# Digital_Port_A_State_LED_Inducator.net
KiCad netlist of a schematic drawn in Altium Designer
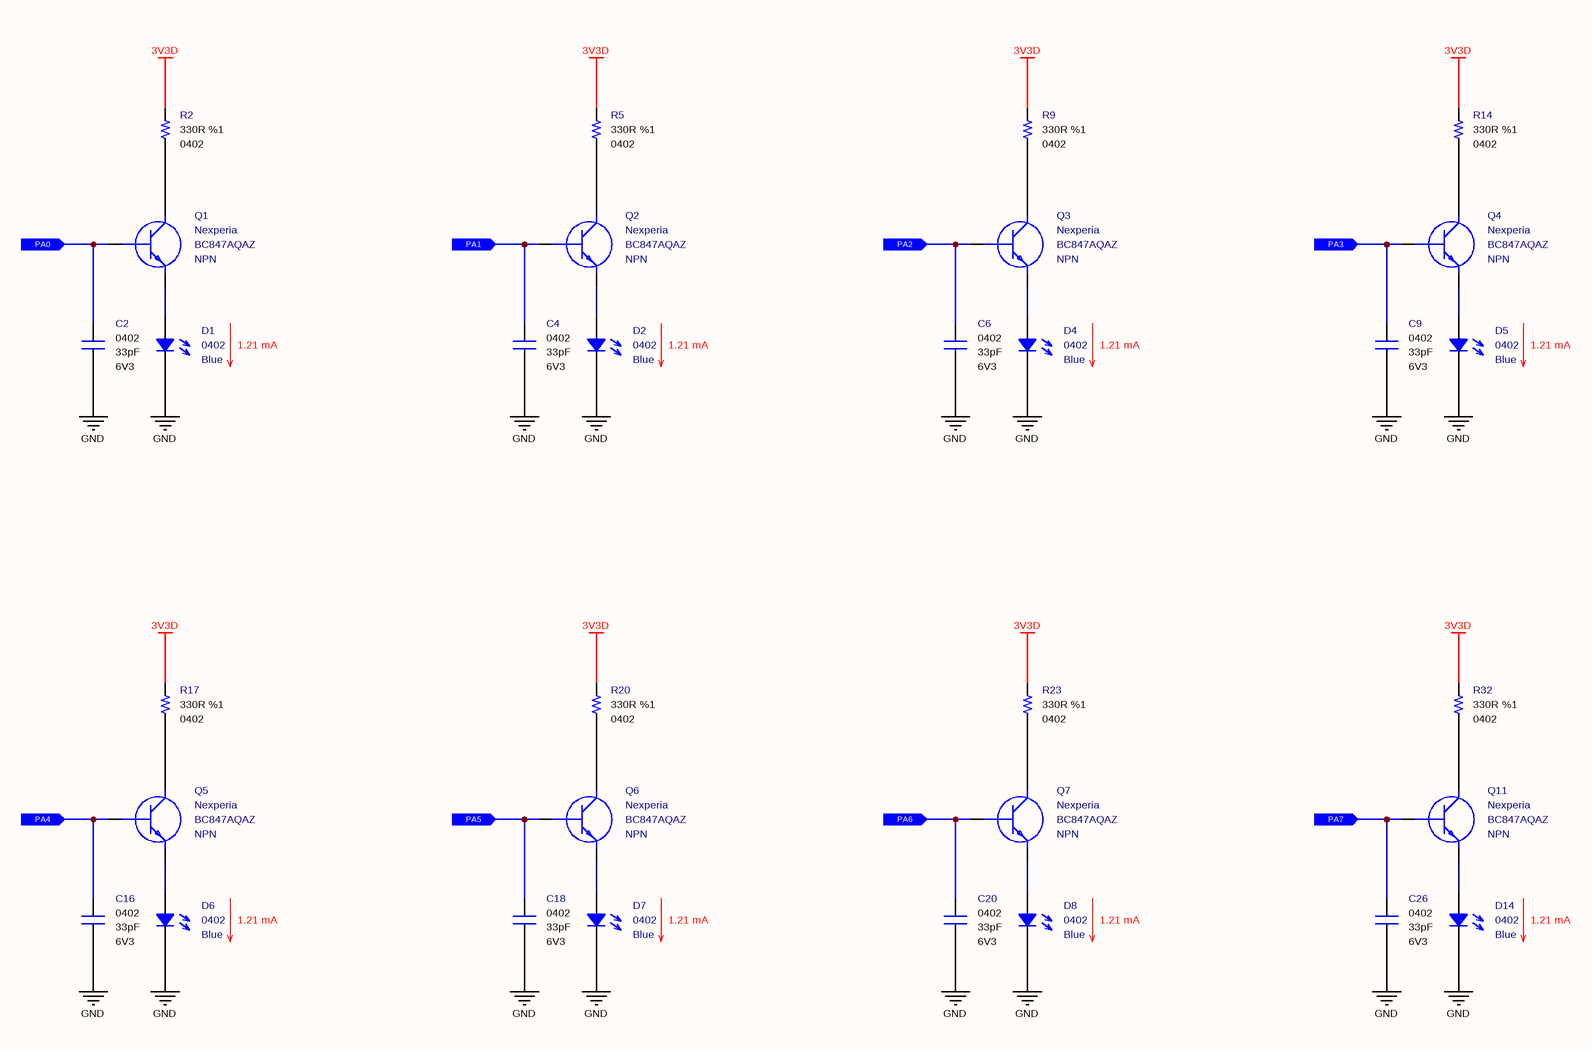
[diagram p0: Digital Port A State LED Inducator.SchDoc]

(export (version "E")
  (design (tool "Eeschema 10.0.6"))
  (components
    (comp (ref "C2")
      (value "33pF")
      (footprint "CAPACITOR_0402")
      (description "Capacitor - 33pF [0402] (Ceramic)")
      (fields
        (field (name "CASE") "0402")
        (field (name "TOLERANCE") "10%")
        (field (name "VOLTAGE") "6V3")
        (field (name "MANUFACTURER PART NUMBER") "C0402C330J9RACAUTO")
      )
      (libsource (lib "Ovoo_Library") (part "Capacitor - 33pF [0402-6V3]"))
    )
    (comp (ref "C4")
      (value "33pF")
      (footprint "CAPACITOR_0402")
      (description "Capacitor - 33pF [0402] (Ceramic)")
      (fields
        (field (name "CASE") "0402")
        (field (name "TOLERANCE") "10%")
        (field (name "VOLTAGE") "6V3")
        (field (name "MANUFACTURER PART NUMBER") "C0402C330J9RACAUTO")
      )
      (libsource (lib "Ovoo_Library") (part "Capacitor - 33pF [0402-6V3]"))
    )
    (comp (ref "C6")
      (value "33pF")
      (footprint "CAPACITOR_0402")
      (description "Capacitor - 33pF [0402] (Ceramic)")
      (fields
        (field (name "CASE") "0402")
        (field (name "TOLERANCE") "10%")
        (field (name "VOLTAGE") "6V3")
        (field (name "MANUFACTURER PART NUMBER") "C0402C330J9RACAUTO")
      )
      (libsource (lib "Ovoo_Library") (part "Capacitor - 33pF [0402-6V3]"))
    )
    (comp (ref "C9")
      (value "33pF")
      (footprint "CAPACITOR_0402")
      (description "Capacitor - 33pF [0402] (Ceramic)")
      (fields
        (field (name "CASE") "0402")
        (field (name "TOLERANCE") "10%")
        (field (name "VOLTAGE") "6V3")
        (field (name "MANUFACTURER PART NUMBER") "C0402C330J9RACAUTO")
      )
      (libsource (lib "Ovoo_Library") (part "Capacitor - 33pF [0402-6V3]"))
    )
    (comp (ref "C16")
      (value "33pF")
      (footprint "CAPACITOR_0402")
      (description "Capacitor - 33pF [0402] (Ceramic)")
      (fields
        (field (name "CASE") "0402")
        (field (name "TOLERANCE") "10%")
        (field (name "VOLTAGE") "6V3")
        (field (name "MANUFACTURER PART NUMBER") "C0402C330J9RACAUTO")
      )
      (libsource (lib "Ovoo_Library") (part "Capacitor - 33pF [0402-6V3]"))
    )
    (comp (ref "C18")
      (value "33pF")
      (footprint "CAPACITOR_0402")
      (description "Capacitor - 33pF [0402] (Ceramic)")
      (fields
        (field (name "CASE") "0402")
        (field (name "TOLERANCE") "10%")
        (field (name "VOLTAGE") "6V3")
        (field (name "MANUFACTURER PART NUMBER") "C0402C330J9RACAUTO")
      )
      (libsource (lib "Ovoo_Library") (part "Capacitor - 33pF [0402-6V3]"))
    )
    (comp (ref "C20")
      (value "33pF")
      (footprint "CAPACITOR_0402")
      (description "Capacitor - 33pF [0402] (Ceramic)")
      (fields
        (field (name "CASE") "0402")
        (field (name "TOLERANCE") "10%")
        (field (name "VOLTAGE") "6V3")
        (field (name "MANUFACTURER PART NUMBER") "C0402C330J9RACAUTO")
      )
      (libsource (lib "Ovoo_Library") (part "Capacitor - 33pF [0402-6V3]"))
    )
    (comp (ref "C26")
      (value "33pF")
      (footprint "CAPACITOR_0402")
      (description "Capacitor - 33pF [0402] (Ceramic)")
      (fields
        (field (name "CASE") "0402")
        (field (name "TOLERANCE") "10%")
        (field (name "VOLTAGE") "6V3")
        (field (name "MANUFACTURER PART NUMBER") "C0402C330J9RACAUTO")
      )
      (libsource (lib "Ovoo_Library") (part "Capacitor - 33pF [0402-6V3]"))
    )
    (comp (ref "D1")
      (value "SMD LED (Blue)")
      (footprint "LED_0402")
      (description "Standard LEDs - SMD PICOLEDTM;BLUE LED; 25M @ 5MA")
      (fields
        (field (name "MANUFACTURER_PART_NUMBER") "SMLP13BC8TT86")
        (field (name "MOUSER_PART_NUMBER") "755-SMLP13BC8TT86")
        (field (name "CASE") "0402")
        (field (name "COLOR") "Blue")
      )
      (libsource (lib "Ovoo_Library") (part "Diode - LED (0402-Blue)"))
    )
    (comp (ref "D2")
      (value "SMD LED (Blue)")
      (footprint "LED_0402")
      (description "Standard LEDs - SMD PICOLEDTM;BLUE LED; 25M @ 5MA")
      (fields
        (field (name "MANUFACTURER_PART_NUMBER") "SMLP13BC8TT86")
        (field (name "MOUSER_PART_NUMBER") "755-SMLP13BC8TT86")
        (field (name "CASE") "0402")
        (field (name "COLOR") "Blue")
      )
      (libsource (lib "Ovoo_Library") (part "Diode - LED (0402-Blue)"))
    )
    (comp (ref "D4")
      (value "SMD LED (Blue)")
      (footprint "LED_0402")
      (description "Standard LEDs - SMD PICOLEDTM;BLUE LED; 25M @ 5MA")
      (fields
        (field (name "MANUFACTURER_PART_NUMBER") "SMLP13BC8TT86")
        (field (name "MOUSER_PART_NUMBER") "755-SMLP13BC8TT86")
        (field (name "CASE") "0402")
        (field (name "COLOR") "Blue")
      )
      (libsource (lib "Ovoo_Library") (part "Diode - LED (0402-Blue)"))
    )
    (comp (ref "D5")
      (value "SMD LED (Blue)")
      (footprint "LED_0402")
      (description "Standard LEDs - SMD PICOLEDTM;BLUE LED; 25M @ 5MA")
      (fields
        (field (name "MANUFACTURER_PART_NUMBER") "SMLP13BC8TT86")
        (field (name "MOUSER_PART_NUMBER") "755-SMLP13BC8TT86")
        (field (name "CASE") "0402")
        (field (name "COLOR") "Blue")
      )
      (libsource (lib "Ovoo_Library") (part "Diode - LED (0402-Blue)"))
    )
    (comp (ref "D6")
      (value "SMD LED (Blue)")
      (footprint "LED_0402")
      (description "Standard LEDs - SMD PICOLEDTM;BLUE LED; 25M @ 5MA")
      (fields
        (field (name "MANUFACTURER_PART_NUMBER") "SMLP13BC8TT86")
        (field (name "MOUSER_PART_NUMBER") "755-SMLP13BC8TT86")
        (field (name "CASE") "0402")
        (field (name "COLOR") "Blue")
      )
      (libsource (lib "Ovoo_Library") (part "Diode - LED (0402-Blue)"))
    )
    (comp (ref "D7")
      (value "SMD LED (Blue)")
      (footprint "LED_0402")
      (description "Standard LEDs - SMD PICOLEDTM;BLUE LED; 25M @ 5MA")
      (fields
        (field (name "MANUFACTURER_PART_NUMBER") "SMLP13BC8TT86")
        (field (name "MOUSER_PART_NUMBER") "755-SMLP13BC8TT86")
        (field (name "CASE") "0402")
        (field (name "COLOR") "Blue")
      )
      (libsource (lib "Ovoo_Library") (part "Diode - LED (0402-Blue)"))
    )
    (comp (ref "D8")
      (value "SMD LED (Blue)")
      (footprint "LED_0402")
      (description "Standard LEDs - SMD PICOLEDTM;BLUE LED; 25M @ 5MA")
      (fields
        (field (name "MANUFACTURER_PART_NUMBER") "SMLP13BC8TT86")
        (field (name "MOUSER_PART_NUMBER") "755-SMLP13BC8TT86")
        (field (name "CASE") "0402")
        (field (name "COLOR") "Blue")
      )
      (libsource (lib "Ovoo_Library") (part "Diode - LED (0402-Blue)"))
    )
    (comp (ref "D14")
      (value "SMD LED (Blue)")
      (footprint "LED_0402")
      (description "Standard LEDs - SMD PICOLEDTM;BLUE LED; 25M @ 5MA")
      (fields
        (field (name "MANUFACTURER_PART_NUMBER") "SMLP13BC8TT86")
        (field (name "MOUSER_PART_NUMBER") "755-SMLP13BC8TT86")
        (field (name "CASE") "0402")
        (field (name "COLOR") "Blue")
      )
      (libsource (lib "Ovoo_Library") (part "Diode - LED (0402-Blue)"))
    )
    (comp (ref "Q1")
      (value "Bipolar NPN Transistors")
      (footprint "SOT1215")
      (description "Bipolar Transistors - BJT BC847AQA/DFN1010D-3/REEL 7\" Q2")
      (fields
        (field (name "MOUSER_PART_NUMBER") "771-BC847AQAZ")
        (field (name "MANUFACTURER_NAME") "Nexperia")
        (field (name "MANUFACTURER_PART_NUMBER") "BC847AQAZ")
        (field (name "POLARITY") "NPN")
      )
      (libsource (lib "Ovoo_Library") (part "Transistor - BC847"))
    )
    (comp (ref "Q2")
      (value "Bipolar NPN Transistors")
      (footprint "SOT1215")
      (description "Bipolar Transistors - BJT BC847AQA/DFN1010D-3/REEL 7\" Q2")
      (fields
        (field (name "MOUSER_PART_NUMBER") "771-BC847AQAZ")
        (field (name "MANUFACTURER_NAME") "Nexperia")
        (field (name "MANUFACTURER_PART_NUMBER") "BC847AQAZ")
        (field (name "POLARITY") "NPN")
      )
      (libsource (lib "Ovoo_Library") (part "Transistor - BC847"))
    )
    (comp (ref "Q3")
      (value "Bipolar NPN Transistors")
      (footprint "SOT1215")
      (description "Bipolar Transistors - BJT BC847AQA/DFN1010D-3/REEL 7\" Q2")
      (fields
        (field (name "MOUSER_PART_NUMBER") "771-BC847AQAZ")
        (field (name "MANUFACTURER_NAME") "Nexperia")
        (field (name "MANUFACTURER_PART_NUMBER") "BC847AQAZ")
        (field (name "POLARITY") "NPN")
      )
      (libsource (lib "Ovoo_Library") (part "Transistor - BC847"))
    )
    (comp (ref "Q4")
      (value "Bipolar NPN Transistors")
      (footprint "SOT1215")
      (description "Bipolar Transistors - BJT BC847AQA/DFN1010D-3/REEL 7\" Q2")
      (fields
        (field (name "MOUSER_PART_NUMBER") "771-BC847AQAZ")
        (field (name "MANUFACTURER_NAME") "Nexperia")
        (field (name "MANUFACTURER_PART_NUMBER") "BC847AQAZ")
        (field (name "POLARITY") "NPN")
      )
      (libsource (lib "Ovoo_Library") (part "Transistor - BC847"))
    )
    (comp (ref "Q5")
      (value "Bipolar NPN Transistors")
      (footprint "SOT1215")
      (description "Bipolar Transistors - BJT BC847AQA/DFN1010D-3/REEL 7\" Q2")
      (fields
        (field (name "MOUSER_PART_NUMBER") "771-BC847AQAZ")
        (field (name "MANUFACTURER_NAME") "Nexperia")
        (field (name "MANUFACTURER_PART_NUMBER") "BC847AQAZ")
        (field (name "POLARITY") "NPN")
      )
      (libsource (lib "Ovoo_Library") (part "Transistor - BC847"))
    )
    (comp (ref "Q6")
      (value "Bipolar NPN Transistors")
      (footprint "SOT1215")
      (description "Bipolar Transistors - BJT BC847AQA/DFN1010D-3/REEL 7\" Q2")
      (fields
        (field (name "MOUSER_PART_NUMBER") "771-BC847AQAZ")
        (field (name "MANUFACTURER_NAME") "Nexperia")
        (field (name "MANUFACTURER_PART_NUMBER") "BC847AQAZ")
        (field (name "POLARITY") "NPN")
      )
      (libsource (lib "Ovoo_Library") (part "Transistor - BC847"))
    )
    (comp (ref "Q7")
      (value "Bipolar NPN Transistors")
      (footprint "SOT1215")
      (description "Bipolar Transistors - BJT BC847AQA/DFN1010D-3/REEL 7\" Q2")
      (fields
        (field (name "MOUSER_PART_NUMBER") "771-BC847AQAZ")
        (field (name "MANUFACTURER_NAME") "Nexperia")
        (field (name "MANUFACTURER_PART_NUMBER") "BC847AQAZ")
        (field (name "POLARITY") "NPN")
      )
      (libsource (lib "Ovoo_Library") (part "Transistor - BC847"))
    )
    (comp (ref "Q11")
      (value "Bipolar NPN Transistors")
      (footprint "SOT1215")
      (description "Bipolar Transistors - BJT BC847AQA/DFN1010D-3/REEL 7\" Q2")
      (fields
        (field (name "MOUSER_PART_NUMBER") "771-BC847AQAZ")
        (field (name "MANUFACTURER_NAME") "Nexperia")
        (field (name "MANUFACTURER_PART_NUMBER") "BC847AQAZ")
        (field (name "POLARITY") "NPN")
      )
      (libsource (lib "Ovoo_Library") (part "Transistor - BC847"))
    )
    (comp (ref "R2")
      (value "330R")
      (footprint "RESISTOR_0402")
      (description "Thick Film Resistors - SMD 1/16 W 330 Ohm 1%")
      (fields
        (field (name "TOLERANCE") "%1")
        (field (name "CASE") "0402")
        (field (name "MANUFACTURER PART NUMBER") "CRCW0402330RFKED")
        (field (name "MOUSER PART NUMBER") "71-CRCW0402-330-E3")
      )
      (libsource (lib "Ovoo_Library") (part "Resistor - 330R"))
    )
    (comp (ref "R5")
      (value "330R")
      (footprint "RESISTOR_0402")
      (description "Thick Film Resistors - SMD 1/16 W 330 Ohm 1%")
      (fields
        (field (name "TOLERANCE") "%1")
        (field (name "CASE") "0402")
        (field (name "MANUFACTURER PART NUMBER") "CRCW0402330RFKED")
        (field (name "MOUSER PART NUMBER") "71-CRCW0402-330-E3")
      )
      (libsource (lib "Ovoo_Library") (part "Resistor - 330R"))
    )
    (comp (ref "R9")
      (value "330R")
      (footprint "RESISTOR_0402")
      (description "Thick Film Resistors - SMD 1/16 W 330 Ohm 1%")
      (fields
        (field (name "TOLERANCE") "%1")
        (field (name "CASE") "0402")
        (field (name "MANUFACTURER PART NUMBER") "CRCW0402330RFKED")
        (field (name "MOUSER PART NUMBER") "71-CRCW0402-330-E3")
      )
      (libsource (lib "Ovoo_Library") (part "Resistor - 330R"))
    )
    (comp (ref "R14")
      (value "330R")
      (footprint "RESISTOR_0402")
      (description "Thick Film Resistors - SMD 1/16 W 330 Ohm 1%")
      (fields
        (field (name "TOLERANCE") "%1")
        (field (name "CASE") "0402")
        (field (name "MANUFACTURER PART NUMBER") "CRCW0402330RFKED")
        (field (name "MOUSER PART NUMBER") "71-CRCW0402-330-E3")
      )
      (libsource (lib "Ovoo_Library") (part "Resistor - 330R"))
    )
    (comp (ref "R17")
      (value "330R")
      (footprint "RESISTOR_0402")
      (description "Thick Film Resistors - SMD 1/16 W 330 Ohm 1%")
      (fields
        (field (name "TOLERANCE") "%1")
        (field (name "CASE") "0402")
        (field (name "MANUFACTURER PART NUMBER") "CRCW0402330RFKED")
        (field (name "MOUSER PART NUMBER") "71-CRCW0402-330-E3")
      )
      (libsource (lib "Ovoo_Library") (part "Resistor - 330R"))
    )
    (comp (ref "R20")
      (value "330R")
      (footprint "RESISTOR_0402")
      (description "Thick Film Resistors - SMD 1/16 W 330 Ohm 1%")
      (fields
        (field (name "TOLERANCE") "%1")
        (field (name "CASE") "0402")
        (field (name "MANUFACTURER PART NUMBER") "CRCW0402330RFKED")
        (field (name "MOUSER PART NUMBER") "71-CRCW0402-330-E3")
      )
      (libsource (lib "Ovoo_Library") (part "Resistor - 330R"))
    )
    (comp (ref "R23")
      (value "330R")
      (footprint "RESISTOR_0402")
      (description "Thick Film Resistors - SMD 1/16 W 330 Ohm 1%")
      (fields
        (field (name "TOLERANCE") "%1")
        (field (name "CASE") "0402")
        (field (name "MANUFACTURER PART NUMBER") "CRCW0402330RFKED")
        (field (name "MOUSER PART NUMBER") "71-CRCW0402-330-E3")
      )
      (libsource (lib "Ovoo_Library") (part "Resistor - 330R"))
    )
    (comp (ref "R32")
      (value "330R")
      (footprint "RESISTOR_0402")
      (description "Thick Film Resistors - SMD 1/16 W 330 Ohm 1%")
      (fields
        (field (name "TOLERANCE") "%1")
        (field (name "CASE") "0402")
        (field (name "MANUFACTURER PART NUMBER") "CRCW0402330RFKED")
        (field (name "MOUSER PART NUMBER") "71-CRCW0402-330-E3")
      )
      (libsource (lib "Ovoo_Library") (part "Resistor - 330R"))
    )
  )
  (nets
    (net (code "1") (name "/PA0") (class "Default")
      (node (ref "C2") (pin "1") (pinfunction "1_1") (pintype "passive"))
      (node (ref "Q1") (pin "1") (pinfunction "B_1") (pintype "passive"))
    )
    (net (code "2") (name "/PA1") (class "Default")
      (node (ref "C4") (pin "1") (pinfunction "1_1") (pintype "passive"))
      (node (ref "Q2") (pin "1") (pinfunction "B_1") (pintype "passive"))
    )
    (net (code "3") (name "/PA2") (class "Default")
      (node (ref "C6") (pin "1") (pinfunction "1_1") (pintype "passive"))
      (node (ref "Q3") (pin "1") (pinfunction "B_1") (pintype "passive"))
    )
    (net (code "4") (name "/PA3") (class "Default")
      (node (ref "C9") (pin "1") (pinfunction "1_1") (pintype "passive"))
      (node (ref "Q4") (pin "1") (pinfunction "B_1") (pintype "passive"))
    )
    (net (code "5") (name "/PA4") (class "Default")
      (node (ref "C16") (pin "1") (pinfunction "1_1") (pintype "passive"))
      (node (ref "Q5") (pin "1") (pinfunction "B_1") (pintype "passive"))
    )
    (net (code "6") (name "/PA5") (class "Default")
      (node (ref "C18") (pin "1") (pinfunction "1_1") (pintype "passive"))
      (node (ref "Q6") (pin "1") (pinfunction "B_1") (pintype "passive"))
    )
    (net (code "7") (name "/PA6") (class "Default")
      (node (ref "C20") (pin "1") (pinfunction "1_1") (pintype "passive"))
      (node (ref "Q7") (pin "1") (pinfunction "B_1") (pintype "passive"))
    )
    (net (code "8") (name "/PA7") (class "Default")
      (node (ref "C26") (pin "1") (pinfunction "1_1") (pintype "passive"))
      (node (ref "Q11") (pin "1") (pinfunction "B_1") (pintype "passive"))
    )
    (net (code "9") (name "3V3D") (class "Default")
      (node (ref "R14") (pin "2") (pinfunction "2_2") (pintype "passive"))
      (node (ref "R17") (pin "2") (pinfunction "2_2") (pintype "passive"))
      (node (ref "R2") (pin "2") (pinfunction "2_2") (pintype "passive"))
      (node (ref "R20") (pin "2") (pinfunction "2_2") (pintype "passive"))
      (node (ref "R23") (pin "2") (pinfunction "2_2") (pintype "passive"))
      (node (ref "R32") (pin "2") (pinfunction "2_2") (pintype "passive"))
      (node (ref "R5") (pin "2") (pinfunction "2_2") (pintype "passive"))
      (node (ref "R9") (pin "2") (pinfunction "2_2") (pintype "passive"))
    )
    (net (code "10") (name "GND") (class "Default")
      (node (ref "C16") (pin "2") (pinfunction "2_2") (pintype "passive"))
      (node (ref "C18") (pin "2") (pinfunction "2_2") (pintype "passive"))
      (node (ref "C2") (pin "2") (pinfunction "2_2") (pintype "passive"))
      (node (ref "C20") (pin "2") (pinfunction "2_2") (pintype "passive"))
      (node (ref "C26") (pin "2") (pinfunction "2_2") (pintype "passive"))
      (node (ref "C4") (pin "2") (pinfunction "2_2") (pintype "passive"))
      (node (ref "C6") (pin "2") (pinfunction "2_2") (pintype "passive"))
      (node (ref "C9") (pin "2") (pinfunction "2_2") (pintype "passive"))
      (node (ref "D1") (pin "1") (pinfunction "1_1") (pintype "passive"))
      (node (ref "D14") (pin "1") (pinfunction "1_1") (pintype "passive"))
      (node (ref "D2") (pin "1") (pinfunction "1_1") (pintype "passive"))
      (node (ref "D4") (pin "1") (pinfunction "1_1") (pintype "passive"))
      (node (ref "D5") (pin "1") (pinfunction "1_1") (pintype "passive"))
      (node (ref "D6") (pin "1") (pinfunction "1_1") (pintype "passive"))
      (node (ref "D7") (pin "1") (pinfunction "1_1") (pintype "passive"))
      (node (ref "D8") (pin "1") (pinfunction "1_1") (pintype "passive"))
    )
    (net (code "11") (name "Net-(Q1-C)") (class "Default")
      (node (ref "Q1") (pin "3") (pinfunction "C_3") (pintype "passive"))
      (node (ref "R2") (pin "1") (pinfunction "1_1") (pintype "passive"))
    )
    (net (code "12") (name "Net-(Q1-E)") (class "Default")
      (node (ref "D1") (pin "2") (pinfunction "2_2") (pintype "passive"))
      (node (ref "Q1") (pin "2") (pinfunction "E_2") (pintype "passive"))
    )
    (net (code "13") (name "Net-(Q2-C)") (class "Default")
      (node (ref "Q2") (pin "3") (pinfunction "C_3") (pintype "passive"))
      (node (ref "R5") (pin "1") (pinfunction "1_1") (pintype "passive"))
    )
    (net (code "14") (name "Net-(Q2-E)") (class "Default")
      (node (ref "D2") (pin "2") (pinfunction "2_2") (pintype "passive"))
      (node (ref "Q2") (pin "2") (pinfunction "E_2") (pintype "passive"))
    )
    (net (code "15") (name "Net-(Q3-C)") (class "Default")
      (node (ref "Q3") (pin "3") (pinfunction "C_3") (pintype "passive"))
      (node (ref "R9") (pin "1") (pinfunction "1_1") (pintype "passive"))
    )
    (net (code "16") (name "Net-(Q3-E)") (class "Default")
      (node (ref "D4") (pin "2") (pinfunction "2_2") (pintype "passive"))
      (node (ref "Q3") (pin "2") (pinfunction "E_2") (pintype "passive"))
    )
    (net (code "17") (name "Net-(Q4-C)") (class "Default")
      (node (ref "Q4") (pin "3") (pinfunction "C_3") (pintype "passive"))
      (node (ref "R14") (pin "1") (pinfunction "1_1") (pintype "passive"))
    )
    (net (code "18") (name "Net-(Q4-E)") (class "Default")
      (node (ref "D5") (pin "2") (pinfunction "2_2") (pintype "passive"))
      (node (ref "Q4") (pin "2") (pinfunction "E_2") (pintype "passive"))
    )
    (net (code "19") (name "Net-(Q5-C)") (class "Default")
      (node (ref "Q5") (pin "3") (pinfunction "C_3") (pintype "passive"))
      (node (ref "R17") (pin "1") (pinfunction "1_1") (pintype "passive"))
    )
    (net (code "20") (name "Net-(Q5-E)") (class "Default")
      (node (ref "D6") (pin "2") (pinfunction "2_2") (pintype "passive"))
      (node (ref "Q5") (pin "2") (pinfunction "E_2") (pintype "passive"))
    )
    (net (code "21") (name "Net-(Q6-C)") (class "Default")
      (node (ref "Q6") (pin "3") (pinfunction "C_3") (pintype "passive"))
      (node (ref "R20") (pin "1") (pinfunction "1_1") (pintype "passive"))
    )
    (net (code "22") (name "Net-(Q6-E)") (class "Default")
      (node (ref "D7") (pin "2") (pinfunction "2_2") (pintype "passive"))
      (node (ref "Q6") (pin "2") (pinfunction "E_2") (pintype "passive"))
    )
    (net (code "23") (name "Net-(Q7-C)") (class "Default")
      (node (ref "Q7") (pin "3") (pinfunction "C_3") (pintype "passive"))
      (node (ref "R23") (pin "1") (pinfunction "1_1") (pintype "passive"))
    )
    (net (code "24") (name "Net-(Q7-E)") (class "Default")
      (node (ref "D8") (pin "2") (pinfunction "2_2") (pintype "passive"))
      (node (ref "Q7") (pin "2") (pinfunction "E_2") (pintype "passive"))
    )
    (net (code "25") (name "Net-(Q11-C)") (class "Default")
      (node (ref "Q11") (pin "3") (pinfunction "C_3") (pintype "passive"))
      (node (ref "R32") (pin "1") (pinfunction "1_1") (pintype "passive"))
    )
    (net (code "26") (name "Net-(Q11-E)") (class "Default")
      (node (ref "D14") (pin "2") (pinfunction "2_2") (pintype "passive"))
      (node (ref "Q11") (pin "2") (pinfunction "E_2") (pintype "passive"))
    )
  )
)
